# wf-np9202-carrier.net
KiCad netlist of a schematic drawn in EAGLE
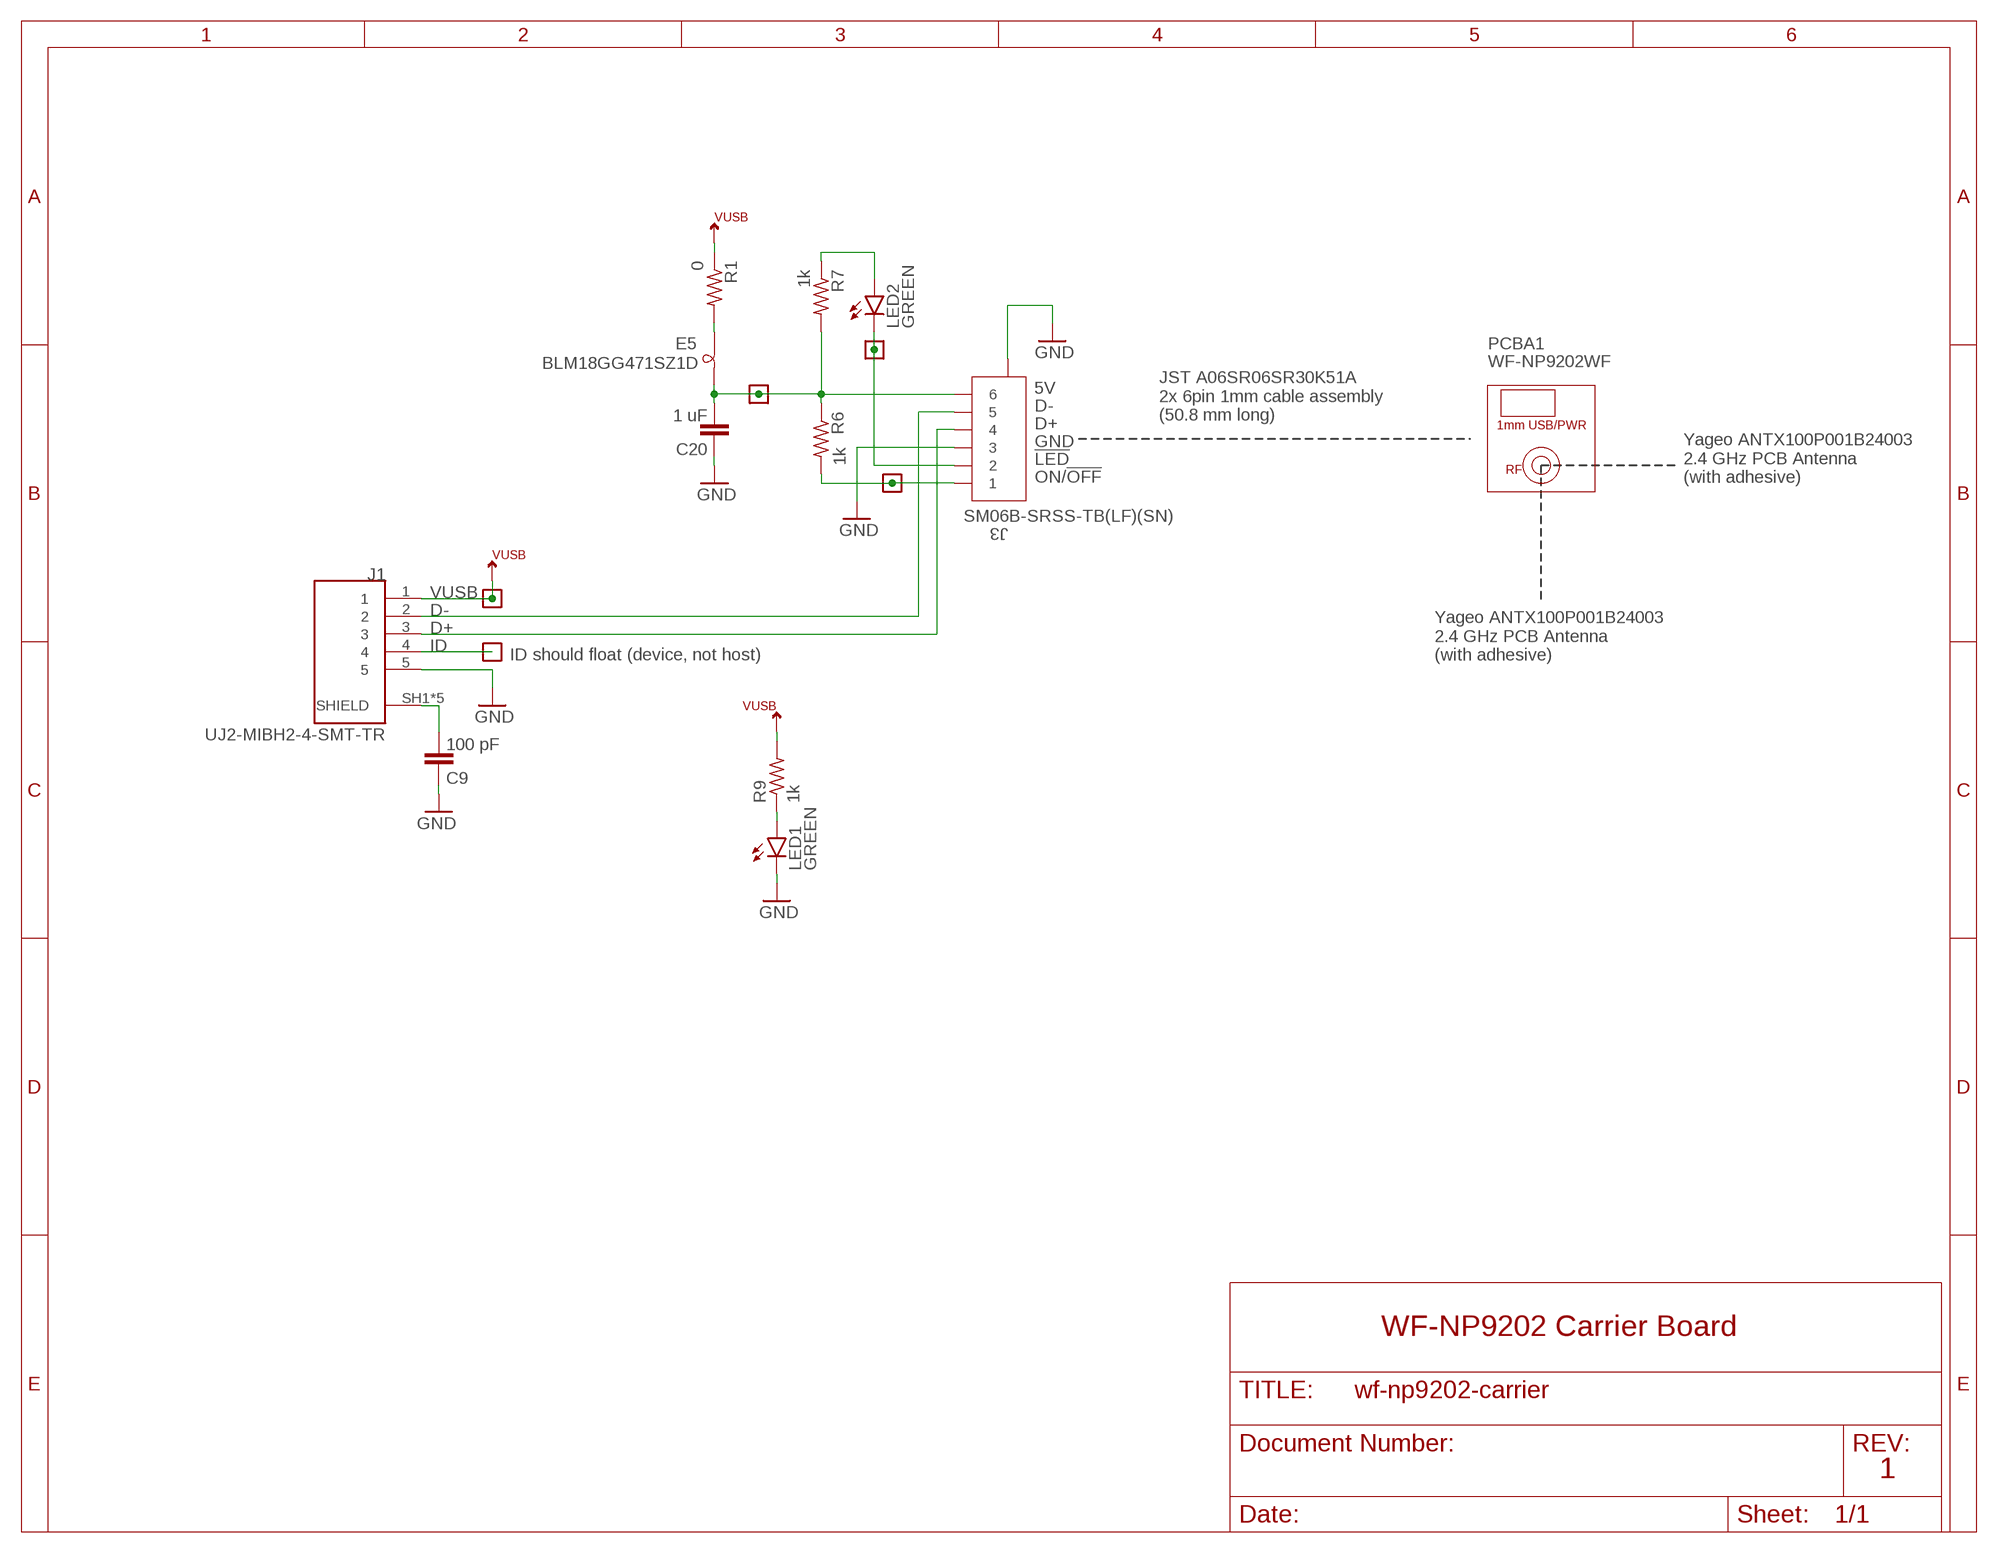
[diagram p0: schematic, sheet 1]

(export (version "E")
  (design (tool "Eeschema 10.0.6"))
  (components
    (comp (ref "C9")
      (value "100 pF")
      (footprint "eagle-import:.0603-C-NOSILK")
      (libsource (lib "eagle-import") (part "C-EU0603-C-NOSILK"))
    )
    (comp (ref "C20")
      (value "1 uF")
      (footprint "eagle-import:.0603-B-NOSILK")
      (libsource (lib "eagle-import") (part "C-EU0603-B-NOSILK"))
    )
    (comp (ref "E5")
      (value "BLM18GG471SZ1D")
      (footprint "eagle-import:.0603-B")
      (libsource (lib "eagle-import") (part "L-BEAD-0603-B"))
    )
    (comp (ref "ID")
      (value "TEST-POINT-LARGE-SQUARE")
      (footprint "eagle-import:1X01")
      (libsource (lib "eagle-import") (part "TEST-POINT-LARGE-SQUARE"))
    )
    (comp (ref "J1")
      (value "UJ2-MIBH2-4-SMT-TR")
      (footprint "eagle-import:CUI_UJ2-MIBH2-4-SMT-TR")
      (fields (field (name "DIGI-KEY_PART_NUMBER") "102-4007-1-ND") (field (name "MF") "CUI Inc."))
      (libsource (lib "eagle-import") (part "UJ2-MIBH2-4-SMT-TR"))
    )
    (comp (ref "J3")
      (value "SM06B-SRSS-TB(LF)(SN)")
      (footprint "eagle-import:CONN_SM06B-SRSS-TB_JST")
      (fields (field (name "COPYRIGHT") "Copyright (C) 2018 Accelerated Designs. All rights reserved"))
      (libsource (lib "eagle-import") (part "SM06B-SRSS-TB(LF)(SN)"))
    )
    (comp (ref "LED1")
      (value "GREEN")
      (footprint "eagle-import:LED-0603")
      (libsource (lib "eagle-import") (part "LED-GREEN0603"))
    )
    (comp (ref "LED2")
      (value "GREEN")
      (footprint "eagle-import:LED-0603")
      (libsource (lib "eagle-import") (part "LED-GREEN0603"))
    )
    (comp (ref "PCBA1")
      (value "WF-NP9202WF")
      (footprint "eagle-import:WF-NP9202")
      (libsource (lib "eagle-import") (part "WF-NP9202WF"))
    )
    (comp (ref "R1")
      (value "0")
      (footprint "eagle-import:.0603-B-NOSILK")
      (libsource (lib "eagle-import") (part "R-US_0603-B-NOSILK"))
    )
    (comp (ref "R6")
      (value "1k")
      (footprint "eagle-import:.0603-B-NOSILK")
      (libsource (lib "eagle-import") (part "R-US_0603-B-NOSILK"))
    )
    (comp (ref "R7")
      (value "1k")
      (footprint "eagle-import:.0603-B-NOSILK")
      (libsource (lib "eagle-import") (part "R-US_0603-B-NOSILK"))
    )
    (comp (ref "R9")
      (value "1k")
      (footprint "eagle-import:.0603-B-NOSILK")
      (libsource (lib "eagle-import") (part "R-US_0603-B-NOSILK"))
    )
    (comp (ref "TP1")
      (value "TEST-POINT-LARGE-SQUARE")
      (footprint "eagle-import:1X01")
      (libsource (lib "eagle-import") (part "TEST-POINT-LARGE-SQUARE"))
    )
    (comp (ref "TP3")
      (value "TEST-POINT-LARGE-SQUARE")
      (footprint "eagle-import:1X01")
      (libsource (lib "eagle-import") (part "TEST-POINT-LARGE-SQUARE"))
    )
    (comp (ref "TP4")
      (value "TEST-POINT-LARGE-SQUARE")
      (footprint "eagle-import:1X01")
      (libsource (lib "eagle-import") (part "TEST-POINT-LARGE-SQUARE"))
    )
    (comp (ref "TP5")
      (value "TEST-POINT-LARGE-SQUARE")
      (footprint "eagle-import:1X01")
      (libsource (lib "eagle-import") (part "TEST-POINT-LARGE-SQUARE"))
    )
  )
  (nets
    (net (code "1") (name "/D+") (class "Default")
      (node (ref "J1") (pin "3") (pinfunction "3_3") (pintype "passive"))
      (node (ref "J3") (pin "4") (pinfunction "4_4") (pintype "passive"))
    )
    (net (code "2") (name "/D-") (class "Default")
      (node (ref "J1") (pin "2") (pinfunction "2_2") (pintype "passive"))
      (node (ref "J3") (pin "5") (pinfunction "5_5") (pintype "passive"))
    )
    (net (code "3") (name "/ID") (class "Default")
      (node (ref "ID") (pin "1") (pinfunction "1_1") (pintype "passive"))
      (node (ref "J1") (pin "4") (pinfunction "4_4") (pintype "passive"))
    )
    (net (code "4") (name "GND") (class "Default")
      (node (ref "C20") (pin "1") (pinfunction "1_1") (pintype "passive"))
      (node (ref "C9") (pin "1") (pinfunction "1_1") (pintype "passive"))
      (node (ref "J1") (pin "5") (pinfunction "5_5") (pintype "passive"))
      (node (ref "J3") (pin "3") (pinfunction "3_3") (pintype "passive"))
      (node (ref "J3") (pin "7") (pinfunction "7_7") (pintype "passive"))
      (node (ref "J3") (pin "8") (pinfunction "7_8") (pintype "passive"))
      (node (ref "LED1") (pin "C") (pinfunction "C_C") (pintype "passive"))
    )
    (net (code "5") (name "Net-(C9-Pad2)") (class "Default")
      (node (ref "C9") (pin "2") (pinfunction "2_2") (pintype "passive"))
      (node (ref "J1") (pin "SH1") (pinfunction "SHIELD_SH1") (pintype "passive"))
      (node (ref "J1") (pin "SH2") (pinfunction "SHIELD_SH2") (pintype "passive"))
      (node (ref "J1") (pin "SH3") (pinfunction "SHIELD_SH3") (pintype "passive"))
      (node (ref "J1") (pin "SH4") (pinfunction "SHIELD_SH4") (pintype "passive"))
      (node (ref "J1") (pin "SH5") (pinfunction "SHIELD_SH5") (pintype "passive"))
    )
    (net (code "6") (name "Net-(C20-Pad2)") (class "Default")
      (node (ref "C20") (pin "2") (pinfunction "2_2") (pintype "passive"))
      (node (ref "E5") (pin "2") (pinfunction "2_2") (pintype "passive"))
      (node (ref "J3") (pin "6") (pinfunction "6_6") (pintype "passive"))
      (node (ref "R6") (pin "1") (pinfunction "1_1") (pintype "passive"))
      (node (ref "R7") (pin "2") (pinfunction "2_2") (pintype "passive"))
      (node (ref "TP3") (pin "1") (pinfunction "1_1") (pintype "passive"))
    )
    (net (code "7") (name "Net-(E5-Pad1)") (class "Default")
      (node (ref "E5") (pin "1") (pinfunction "1_1") (pintype "passive"))
      (node (ref "R1") (pin "2") (pinfunction "2_2") (pintype "passive"))
    )
    (net (code "8") (name "Net-(J3-Pad1)") (class "Default")
      (node (ref "J3") (pin "1") (pinfunction "1_1") (pintype "passive"))
      (node (ref "R6") (pin "2") (pinfunction "2_2") (pintype "passive"))
      (node (ref "TP4") (pin "1") (pinfunction "1_1") (pintype "passive"))
    )
    (net (code "9") (name "Net-(J3-Pad2)") (class "Default")
      (node (ref "J3") (pin "2") (pinfunction "2_2") (pintype "passive"))
      (node (ref "LED2") (pin "C") (pinfunction "C_C") (pintype "passive"))
      (node (ref "TP5") (pin "1") (pinfunction "1_1") (pintype "passive"))
    )
    (net (code "10") (name "Net-(LED1-PadA)") (class "Default")
      (node (ref "LED1") (pin "A") (pinfunction "A_A") (pintype "passive"))
      (node (ref "R9") (pin "1") (pinfunction "1_1") (pintype "passive"))
    )
    (net (code "11") (name "Net-(LED2-PadA)") (class "Default")
      (node (ref "LED2") (pin "A") (pinfunction "A_A") (pintype "passive"))
      (node (ref "R7") (pin "1") (pinfunction "1_1") (pintype "passive"))
    )
    (net (code "12") (name "VUSB") (class "Default")
      (node (ref "J1") (pin "1") (pinfunction "1_1") (pintype "passive"))
      (node (ref "R1") (pin "1") (pinfunction "1_1") (pintype "passive"))
      (node (ref "R9") (pin "2") (pinfunction "2_2") (pintype "passive"))
      (node (ref "TP1") (pin "1") (pinfunction "1_1") (pintype "passive"))
    )
  )
)
